# ETA9640.net
KiCad netlist of a schematic drawn in Altium Designer
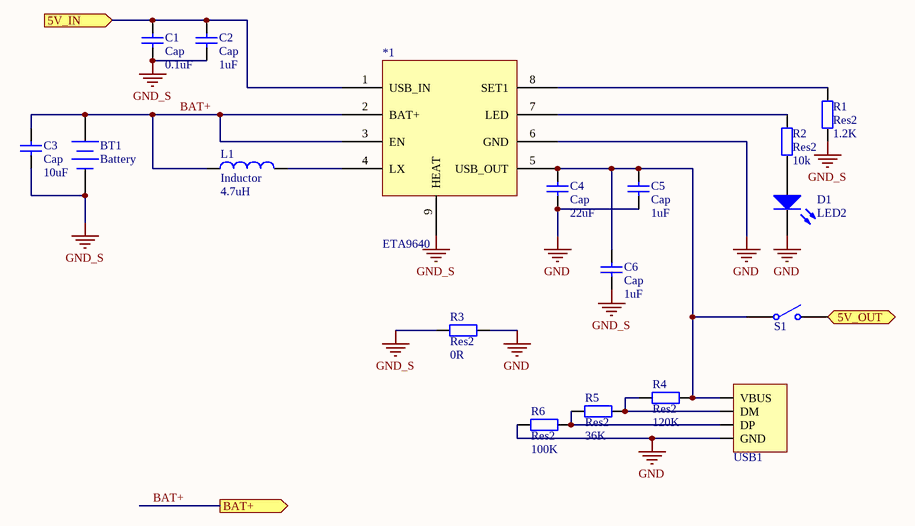
[diagram p0: ETA9640.SchDoc]

(export (version "E")
  (design (tool "Eeschema 10.0.6"))
  (components
    (comp (ref "*1") (value "ETA9640") (footprint "ESOP-8") (libsource (lib "POWERS") (part "ETA9640")))
    (comp (ref "BT1")
      (value "Battery")
      (footprint "BAT-2")
      (description "Multicell Battery")
      (fields (field (name "PUBLISHER") "Altium Limited"))
      (libsource (lib "Miscellaneous Devices") (part "Battery"))
    )
    (comp (ref "C1")
      (value "Cap")
      (footprint "CAP_0603")
      (description "Capacitor")
      (fields (field (name "ALTIUM_VALUE") "0.1uF") (field (name "PUBLISHER") "Altium Limited"))
      (libsource (lib "Miscellaneous Devices") (part "Cap"))
    )
    (comp (ref "C2")
      (value "Cap")
      (footprint "CAP_0603")
      (description "Capacitor")
      (fields (field (name "ALTIUM_VALUE") "1uF") (field (name "PUBLISHER") "Altium Limited"))
      (libsource (lib "Miscellaneous Devices") (part "Cap"))
    )
    (comp (ref "C3")
      (value "Cap")
      (footprint "1206")
      (description "Capacitor")
      (fields (field (name "ALTIUM_VALUE") "10uF") (field (name "PUBLISHER") "Altium Limited"))
      (libsource (lib "Miscellaneous Devices") (part "Cap"))
    )
    (comp (ref "C4")
      (value "Cap")
      (footprint "1206")
      (description "Capacitor")
      (fields (field (name "ALTIUM_VALUE") "22uF") (field (name "PUBLISHER") "Altium Limited"))
      (libsource (lib "Miscellaneous Devices") (part "Cap"))
    )
    (comp (ref "C5")
      (value "Cap")
      (footprint "CAP_0603")
      (description "Capacitor")
      (fields (field (name "ALTIUM_VALUE") "1uF") (field (name "PUBLISHER") "Altium Limited"))
      (libsource (lib "Miscellaneous Devices") (part "Cap"))
    )
    (comp (ref "C6")
      (value "Cap")
      (footprint "CAP_0603")
      (description "Capacitor")
      (fields (field (name "ALTIUM_VALUE") "1uF") (field (name "PUBLISHER") "Altium Limited"))
      (libsource (lib "Miscellaneous Devices") (part "Cap"))
    )
    (comp (ref "D1")
      (value "LED2")
      (footprint "LED_0603_RED")
      (description "Typical RED, GREEN, YELLOW, AMBER GaAs LED")
      (fields (field (name "PUBLISHER") "Altium Limited"))
      (libsource (lib "Miscellaneous Devices") (part "LED2"))
    )
    (comp (ref "L1")
      (value "Inductor")
      (footprint "VLF4012_2R2")
      (fields (field (name "ALTIUM_VALUE") "4.7uH") (field (name "PUBLISHER") "Altium Limited"))
      (libsource (lib "Miscellaneous Devices") (part "Inductor"))
    )
    (comp (ref "R1")
      (value "Res2")
      (footprint "RES_0603")
      (description "Resistor")
      (fields (field (name "ALTIUM_VALUE") "1.2K") (field (name "PUBLISHER") "Altium Limited"))
      (libsource (lib "") (part "Res2_1"))
    )
    (comp (ref "R2")
      (value "Res2")
      (footprint "RES_0603")
      (description "Resistor")
      (fields (field (name "ALTIUM_VALUE") "10k") (field (name "PUBLISHER") "Altium Limited"))
      (libsource (lib "") (part "Res2_1"))
    )
    (comp (ref "R3")
      (value "Res2")
      (footprint "RES_0603")
      (description "Resistor")
      (fields (field (name "ALTIUM_VALUE") "0R") (field (name "PUBLISHER") "Altium Limited"))
      (libsource (lib "") (part "Res2_2"))
    )
    (comp (ref "R4")
      (value "Res2")
      (footprint "RES_0603")
      (description "Resistor")
      (fields (field (name "ALTIUM_VALUE") "120K") (field (name "PUBLISHER") "Altium Limited"))
      (libsource (lib "Miscellaneous Devices") (part "Res2"))
    )
    (comp (ref "R5")
      (value "Res2")
      (footprint "RES_0603")
      (description "Resistor")
      (fields (field (name "ALTIUM_VALUE") "36K") (field (name "PUBLISHER") "Altium Limited"))
      (libsource (lib "Miscellaneous Devices") (part "Res2"))
    )
    (comp (ref "R6")
      (value "Res2")
      (footprint "RES_0603")
      (description "Resistor")
      (fields (field (name "ALTIUM_VALUE") "100K") (field (name "PUBLISHER") "Altium Limited"))
      (libsource (lib "Miscellaneous Devices") (part "Res2"))
    )
    (comp (ref "S1")
      (value "SW-SPST")
      (footprint "SB-4")
      (description "Single-Pole, Single-Throw Switch")
      (fields (field (name "PUBLISHER") "Altium Limited"))
      (libsource (lib "POWERS") (part "SW-SPST"))
    )
    (comp (ref "USB1") (value "USB") (footprint "USB") (libsource (lib "POWERS") (part "USB")))
  )
  (nets
    (net (code "1") (name "/5V_IN") (class "Default")
      (node (ref "*1") (pin "1") (pinfunction "USB_IN_1") (pintype "passive"))
      (node (ref "C1") (pin "2") (pinfunction "2_2") (pintype "passive"))
      (node (ref "C2") (pin "2") (pinfunction "2_2") (pintype "passive"))
    )
    (net (code "2") (name "/5V_OUT") (class "Default")
      (node (ref "S1") (pin "2") (pinfunction "NO_2") (pintype "passive"))
    )
    (net (code "3") (name "/BAT+") (class "Default")
      (node (ref "*1") (pin "2") (pinfunction "BAT+_2") (pintype "passive"))
      (node (ref "*1") (pin "3") (pinfunction "EN_3") (pintype "passive"))
      (node (ref "BT1") (pin "1") (pinfunction "+_1") (pintype "passive"))
      (node (ref "C3") (pin "2") (pinfunction "2_2") (pintype "passive"))
      (node (ref "L1") (pin "1") (pinfunction "1_1") (pintype "passive"))
    )
    (net (code "4") (name "GND") (class "Default")
      (node (ref "*1") (pin "6") (pinfunction "GND_6") (pintype "passive"))
      (node (ref "C4") (pin "1") (pinfunction "1_1") (pintype "passive"))
      (node (ref "C5") (pin "1") (pinfunction "1_1") (pintype "passive"))
      (node (ref "D1") (pin "2") (pinfunction "K_2") (pintype "passive"))
      (node (ref "R3") (pin "1") (pinfunction "1_1") (pintype "passive"))
      (node (ref "R6") (pin "1") (pinfunction "1_1") (pintype "passive"))
      (node (ref "USB1") (pin "-") (pinfunction "GND_-") (pintype "passive"))
    )
    (net (code "5") (name "GND_S") (class "Default")
      (node (ref "*1") (pin "9") (pinfunction "HEAT_9") (pintype "passive"))
      (node (ref "BT1") (pin "2") (pinfunction "-_2") (pintype "passive"))
      (node (ref "C1") (pin "1") (pinfunction "1_1") (pintype "passive"))
      (node (ref "C2") (pin "1") (pinfunction "1_1") (pintype "passive"))
      (node (ref "C3") (pin "1") (pinfunction "1_1") (pintype "passive"))
      (node (ref "C6") (pin "1") (pinfunction "1_1") (pintype "passive"))
      (node (ref "R1") (pin "1") (pinfunction "1_1") (pintype "passive"))
      (node (ref "R3") (pin "2") (pinfunction "2_2") (pintype "passive"))
    )
    (net (code "6") (name "Net-(*1-LED)") (class "Default")
      (node (ref "*1") (pin "7") (pinfunction "LED_7") (pintype "passive"))
      (node (ref "R2") (pin "2") (pinfunction "2_2") (pintype "passive"))
    )
    (net (code "7") (name "Net-(*1-LX)") (class "Default")
      (node (ref "*1") (pin "4") (pinfunction "LX_4") (pintype "passive"))
      (node (ref "L1") (pin "2") (pinfunction "2_2") (pintype "passive"))
    )
    (net (code "8") (name "Net-(*1-SET1)") (class "Default")
      (node (ref "*1") (pin "8") (pinfunction "SET1_8") (pintype "passive"))
      (node (ref "R1") (pin "2") (pinfunction "2_2") (pintype "passive"))
    )
    (net (code "9") (name "Net-(*1-USB_OUT)") (class "Default")
      (node (ref "*1") (pin "5") (pinfunction "USB_OUT_5") (pintype "passive"))
      (node (ref "C4") (pin "2") (pinfunction "2_2") (pintype "passive"))
      (node (ref "C5") (pin "2") (pinfunction "2_2") (pintype "passive"))
      (node (ref "C6") (pin "2") (pinfunction "2_2") (pintype "passive"))
      (node (ref "R4") (pin "2") (pinfunction "2_2") (pintype "passive"))
      (node (ref "S1") (pin "1") (pinfunction "COMMON_1") (pintype "passive"))
      (node (ref "USB1") (pin "+") (pinfunction "VBUS_+") (pintype "passive"))
    )
    (net (code "10") (name "Net-(D1-A)") (class "Default")
      (node (ref "D1") (pin "1") (pinfunction "A_1") (pintype "passive"))
      (node (ref "R2") (pin "1") (pinfunction "1_1") (pintype "passive"))
    )
    (net (code "11") (name "Net-(R4-Pad1)") (class "Default")
      (node (ref "R4") (pin "1") (pinfunction "1_1") (pintype "passive"))
      (node (ref "R5") (pin "2") (pinfunction "2_2") (pintype "passive"))
      (node (ref "USB1") (pin "DM") (pinfunction "DM_DM") (pintype "passive"))
    )
    (net (code "12") (name "Net-(R5-Pad1)") (class "Default")
      (node (ref "R5") (pin "1") (pinfunction "1_1") (pintype "passive"))
      (node (ref "R6") (pin "2") (pinfunction "2_2") (pintype "passive"))
      (node (ref "USB1") (pin "DP") (pinfunction "DP_DP") (pintype "passive"))
    )
  )
)
